# Sheet1_02_21_dongho.net
KiCad netlist of a schematic drawn in Altium Designer
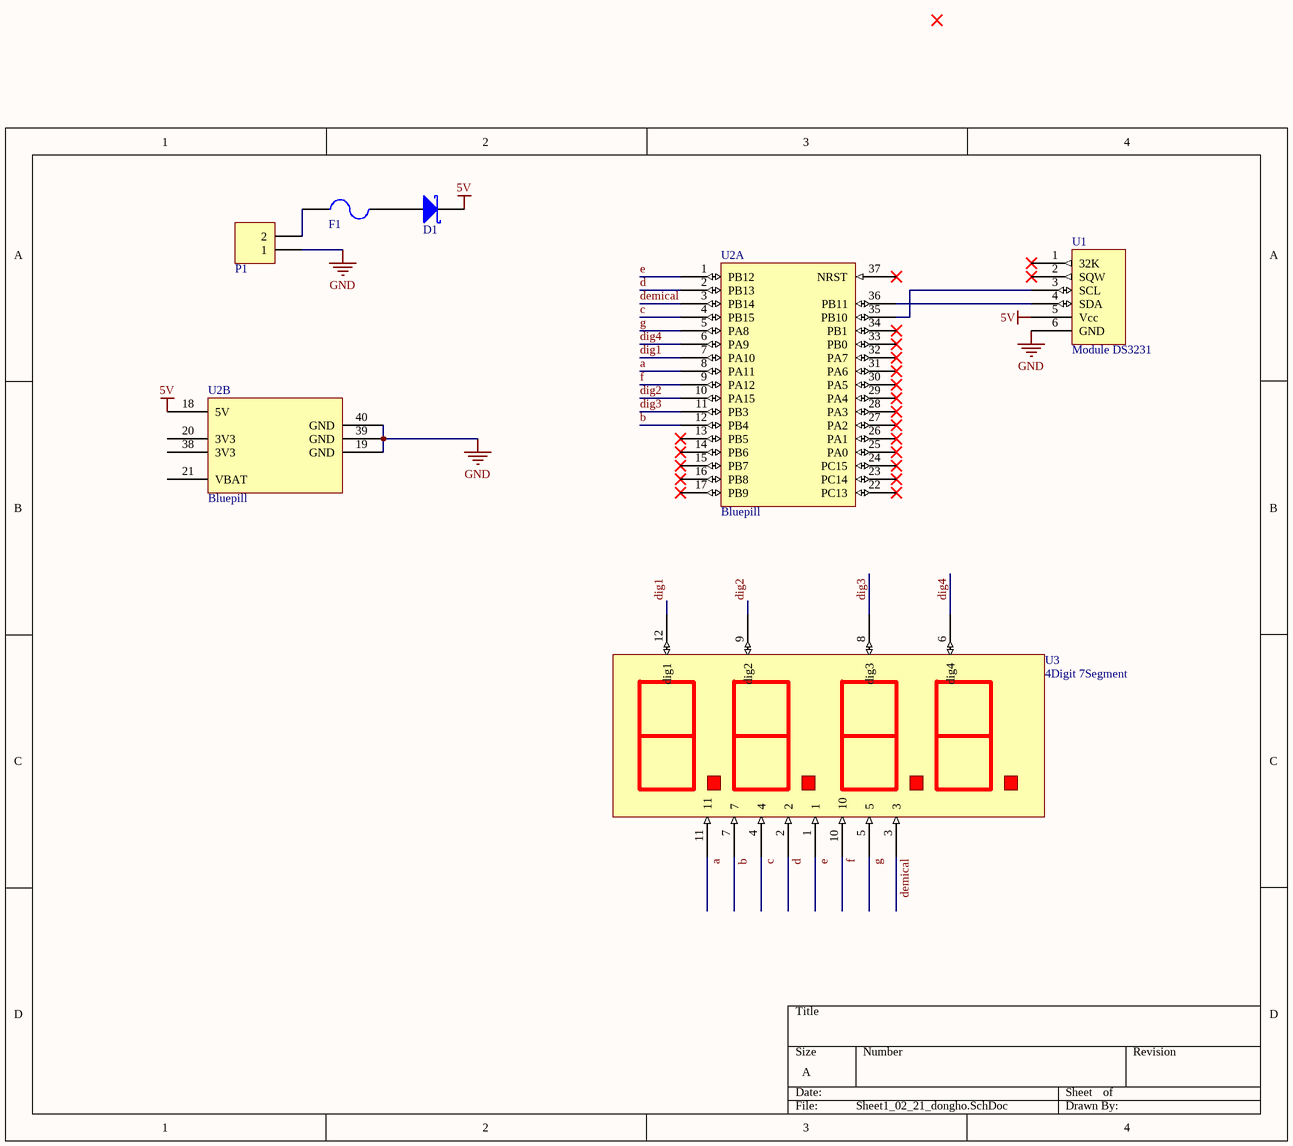
[diagram p0: Sheet1_02_21_dongho.SchDoc]

(export (version "E")
  (design (tool "Eeschema 10.0.6"))
  (components
    (comp (ref "D1")
      (value "D Schottky")
      (footprint "SS34")
      (description "Schottky Diode")
      (fields (field (name "PUBLISHER") "Altium Limited"))
      (libsource (lib "PIF_Library") (part "D Schottky"))
    )
    (comp (ref "F1") (value "Fuse") (footprint "FUSE SMD") (libsource (lib "PIF_Library") (part "Fuse")))
    (comp (ref "P1")
      (value "Domino 2")
      (footprint "DOMINO 2- 5mm")
      (description "Domino, 2-Pin")
      (fields (field (name "PUBLISHER") "Altium Limited"))
      (libsource (lib "PIF_Library") (part "Domino 2"))
    )
    (comp (ref "U1")
      (value "Module DS3231")
      (footprint "Module DS3231( Part A )")
      (libsource (lib "230215_PIFProject_LibPCB_Tvy_v") (part "DS3231"))
    )
    (comp (ref "U2")
      (value "Bluepill")
      (footprint "Blue Pill")
      (description "STM32F103C8T6")
      (libsource (lib "Bluepill") (part "STM32F103C8T6"))
    )
    (comp (ref "U3")
      (value "4Digit 7Segment")
      (footprint "4 digit 7 segment")
      (description "4 digit 7 segment ( Anot chung)")
      (libsource (lib "Integrated_Library2_thuvienB1") (part "4Digit 7Segment"))
    )
  )
  (nets
    (net (code "1") (name "/a") (class "Default")
      (node (ref "U2") (pin "8") (pinfunction "PA11_8") (pintype "bidirectional"))
      (node (ref "U3") (pin "11") (pinfunction "11_11") (pintype "input"))
    )
    (net (code "2") (name "/b") (class "Default")
      (node (ref "U2") (pin "12") (pinfunction "PB4_12") (pintype "bidirectional"))
      (node (ref "U3") (pin "7") (pinfunction "7_7") (pintype "input"))
    )
    (net (code "3") (name "/c") (class "Default")
      (node (ref "U2") (pin "4") (pinfunction "PB15_4") (pintype "bidirectional"))
      (node (ref "U3") (pin "4") (pinfunction "4_4") (pintype "input"))
    )
    (net (code "4") (name "/d") (class "Default")
      (node (ref "U2") (pin "2") (pinfunction "PB13_2") (pintype "bidirectional"))
      (node (ref "U3") (pin "2") (pinfunction "2_2") (pintype "input"))
    )
    (net (code "5") (name "/demical") (class "Default")
      (node (ref "U2") (pin "3") (pinfunction "PB14_3") (pintype "bidirectional"))
      (node (ref "U3") (pin "3") (pinfunction "3_3") (pintype "input"))
    )
    (net (code "6") (name "/dig1") (class "Default")
      (node (ref "U2") (pin "7") (pinfunction "PA10_7") (pintype "bidirectional"))
      (node (ref "U3") (pin "12") (pinfunction "dig1_12") (pintype "bidirectional"))
    )
    (net (code "7") (name "/dig2") (class "Default")
      (node (ref "U2") (pin "10") (pinfunction "PA15_10") (pintype "bidirectional"))
      (node (ref "U3") (pin "9") (pinfunction "dig2_9") (pintype "bidirectional"))
    )
    (net (code "8") (name "/dig3") (class "Default")
      (node (ref "U2") (pin "11") (pinfunction "PB3_11") (pintype "bidirectional"))
      (node (ref "U3") (pin "8") (pinfunction "dig3_8") (pintype "bidirectional"))
    )
    (net (code "9") (name "/dig4") (class "Default")
      (node (ref "U2") (pin "6") (pinfunction "PA9_6") (pintype "bidirectional"))
      (node (ref "U3") (pin "6") (pinfunction "dig4_6") (pintype "bidirectional"))
    )
    (net (code "10") (name "/e") (class "Default")
      (node (ref "U2") (pin "1") (pinfunction "PB12_1") (pintype "bidirectional"))
      (node (ref "U3") (pin "1") (pinfunction "1_1") (pintype "input"))
    )
    (net (code "11") (name "/f") (class "Default")
      (node (ref "U2") (pin "9") (pinfunction "PA12_9") (pintype "bidirectional"))
      (node (ref "U3") (pin "10") (pinfunction "10_10") (pintype "input"))
    )
    (net (code "12") (name "/g") (class "Default")
      (node (ref "U2") (pin "5") (pinfunction "PA8_5") (pintype "bidirectional"))
      (node (ref "U3") (pin "5") (pinfunction "5_5") (pintype "input"))
    )
    (net (code "13") (name "5V") (class "Default")
      (node (ref "D1") (pin "2") (pinfunction "K_2") (pintype "passive"))
      (node (ref "U1") (pin "5") (pinfunction "Vcc_5") (pintype "power_in"))
      (node (ref "U2") (pin "18") (pinfunction "5V_18") (pintype "power_in"))
    )
    (net (code "14") (name "GND") (class "Default")
      (node (ref "P1") (pin "1") (pinfunction "1_1") (pintype "passive"))
      (node (ref "U1") (pin "6") (pinfunction "GND_6") (pintype "power_in"))
      (node (ref "U2") (pin "19") (pinfunction "GND_19") (pintype "power_in"))
      (node (ref "U2") (pin "39") (pinfunction "GND_39") (pintype "power_in"))
      (node (ref "U2") (pin "40") (pinfunction "GND_40") (pintype "power_in"))
    )
    (net (code "15") (name "Net-(D1-A)") (class "Default")
      (node (ref "D1") (pin "1") (pinfunction "A_1") (pintype "passive"))
      (node (ref "F1") (pin "2") (pinfunction "2_2") (pintype "passive"))
    )
    (net (code "16") (name "Net-(F1-Pad1)") (class "Default")
      (node (ref "F1") (pin "1") (pinfunction "1_1") (pintype "passive"))
      (node (ref "P1") (pin "2") (pinfunction "2_2") (pintype "passive"))
    )
    (net (code "17") (name "Net-(U1-SCL)") (class "Default")
      (node (ref "U1") (pin "3") (pinfunction "SCL_3") (pintype "bidirectional"))
      (node (ref "U2") (pin "35") (pinfunction "PB10_35") (pintype "bidirectional"))
    )
    (net (code "18") (name "Net-(U1-SDA)") (class "Default")
      (node (ref "U1") (pin "4") (pinfunction "SDA_4") (pintype "bidirectional"))
      (node (ref "U2") (pin "36") (pinfunction "PB11_36") (pintype "bidirectional"))
    )
    (net (code "19") (name "unconnected-(U1-32K-Pad1)") (class "Default")
      (node (ref "U1") (pin "1") (pinfunction "32K_1") (pintype "output+no_connect"))
    )
    (net (code "20") (name "unconnected-(U1-SQW-Pad2)") (class "Default")
      (node (ref "U1") (pin "2") (pinfunction "SQW_2") (pintype "output+no_connect"))
    )
    (net (code "21") (name "unconnected-(U2A-NRST-Pad37)") (class "Default")
      (node (ref "U2") (pin "37") (pinfunction "NRST_37") (pintype "input+no_connect"))
    )
    (net (code "22") (name "unconnected-(U2A-PA0-Pad25)") (class "Default")
      (node (ref "U2") (pin "25") (pinfunction "PA0_25") (pintype "bidirectional+no_connect"))
    )
    (net (code "23") (name "unconnected-(U2A-PA1-Pad26)") (class "Default")
      (node (ref "U2") (pin "26") (pinfunction "PA1_26") (pintype "bidirectional+no_connect"))
    )
    (net (code "24") (name "unconnected-(U2A-PA2-Pad27)") (class "Default")
      (node (ref "U2") (pin "27") (pinfunction "PA2_27") (pintype "bidirectional+no_connect"))
    )
    (net (code "25") (name "unconnected-(U2A-PA3-Pad28)") (class "Default")
      (node (ref "U2") (pin "28") (pinfunction "PA3_28") (pintype "bidirectional+no_connect"))
    )
    (net (code "26") (name "unconnected-(U2A-PA4-Pad29)") (class "Default")
      (node (ref "U2") (pin "29") (pinfunction "PA4_29") (pintype "bidirectional+no_connect"))
    )
    (net (code "27") (name "unconnected-(U2A-PA5-Pad30)") (class "Default")
      (node (ref "U2") (pin "30") (pinfunction "PA5_30") (pintype "bidirectional+no_connect"))
    )
    (net (code "28") (name "unconnected-(U2A-PA6-Pad31)") (class "Default")
      (node (ref "U2") (pin "31") (pinfunction "PA6_31") (pintype "bidirectional+no_connect"))
    )
    (net (code "29") (name "unconnected-(U2A-PA7-Pad32)") (class "Default")
      (node (ref "U2") (pin "32") (pinfunction "PA7_32") (pintype "bidirectional+no_connect"))
    )
    (net (code "30") (name "unconnected-(U2A-PB0-Pad33)") (class "Default")
      (node (ref "U2") (pin "33") (pinfunction "PB0_33") (pintype "bidirectional+no_connect"))
    )
    (net (code "31") (name "unconnected-(U2A-PB1-Pad34)") (class "Default")
      (node (ref "U2") (pin "34") (pinfunction "PB1_34") (pintype "bidirectional+no_connect"))
    )
    (net (code "32") (name "unconnected-(U2A-PB5-Pad13)") (class "Default")
      (node (ref "U2") (pin "13") (pinfunction "PB5_13") (pintype "bidirectional+no_connect"))
    )
    (net (code "33") (name "unconnected-(U2A-PB6-Pad14)") (class "Default")
      (node (ref "U2") (pin "14") (pinfunction "PB6_14") (pintype "bidirectional+no_connect"))
    )
    (net (code "34") (name "unconnected-(U2A-PB7-Pad15)") (class "Default")
      (node (ref "U2") (pin "15") (pinfunction "PB7_15") (pintype "bidirectional+no_connect"))
    )
    (net (code "35") (name "unconnected-(U2A-PB8-Pad16)") (class "Default")
      (node (ref "U2") (pin "16") (pinfunction "PB8_16") (pintype "bidirectional+no_connect"))
    )
    (net (code "36") (name "unconnected-(U2A-PB9-Pad17)") (class "Default")
      (node (ref "U2") (pin "17") (pinfunction "PB9_17") (pintype "bidirectional+no_connect"))
    )
    (net (code "37") (name "unconnected-(U2A-PC13-Pad22)") (class "Default")
      (node (ref "U2") (pin "22") (pinfunction "PC13_22") (pintype "bidirectional+no_connect"))
    )
    (net (code "38") (name "unconnected-(U2A-PC14-Pad23)") (class "Default")
      (node (ref "U2") (pin "23") (pinfunction "PC14_23") (pintype "bidirectional+no_connect"))
    )
    (net (code "39") (name "unconnected-(U2A-PC15-Pad24)") (class "Default")
      (node (ref "U2") (pin "24") (pinfunction "PC15_24") (pintype "bidirectional+no_connect"))
    )
    (net (code "40") (name "unconnected-(U2B-3V3-Pad20)") (class "Default")
      (node (ref "U2") (pin "20") (pinfunction "3V3_20") (pintype "power_in"))
    )
    (net (code "41") (name "unconnected-(U2B-3V3-Pad38)") (class "Default")
      (node (ref "U2") (pin "38") (pinfunction "3V3_38") (pintype "power_in"))
    )
    (net (code "42") (name "unconnected-(U2B-VBAT-Pad21)") (class "Default")
      (node (ref "U2") (pin "21") (pinfunction "VBAT_21") (pintype "power_in"))
    )
  )
)
